# Power_Amp_V1_0.net
KiCad netlist of a schematic drawn in EAGLE
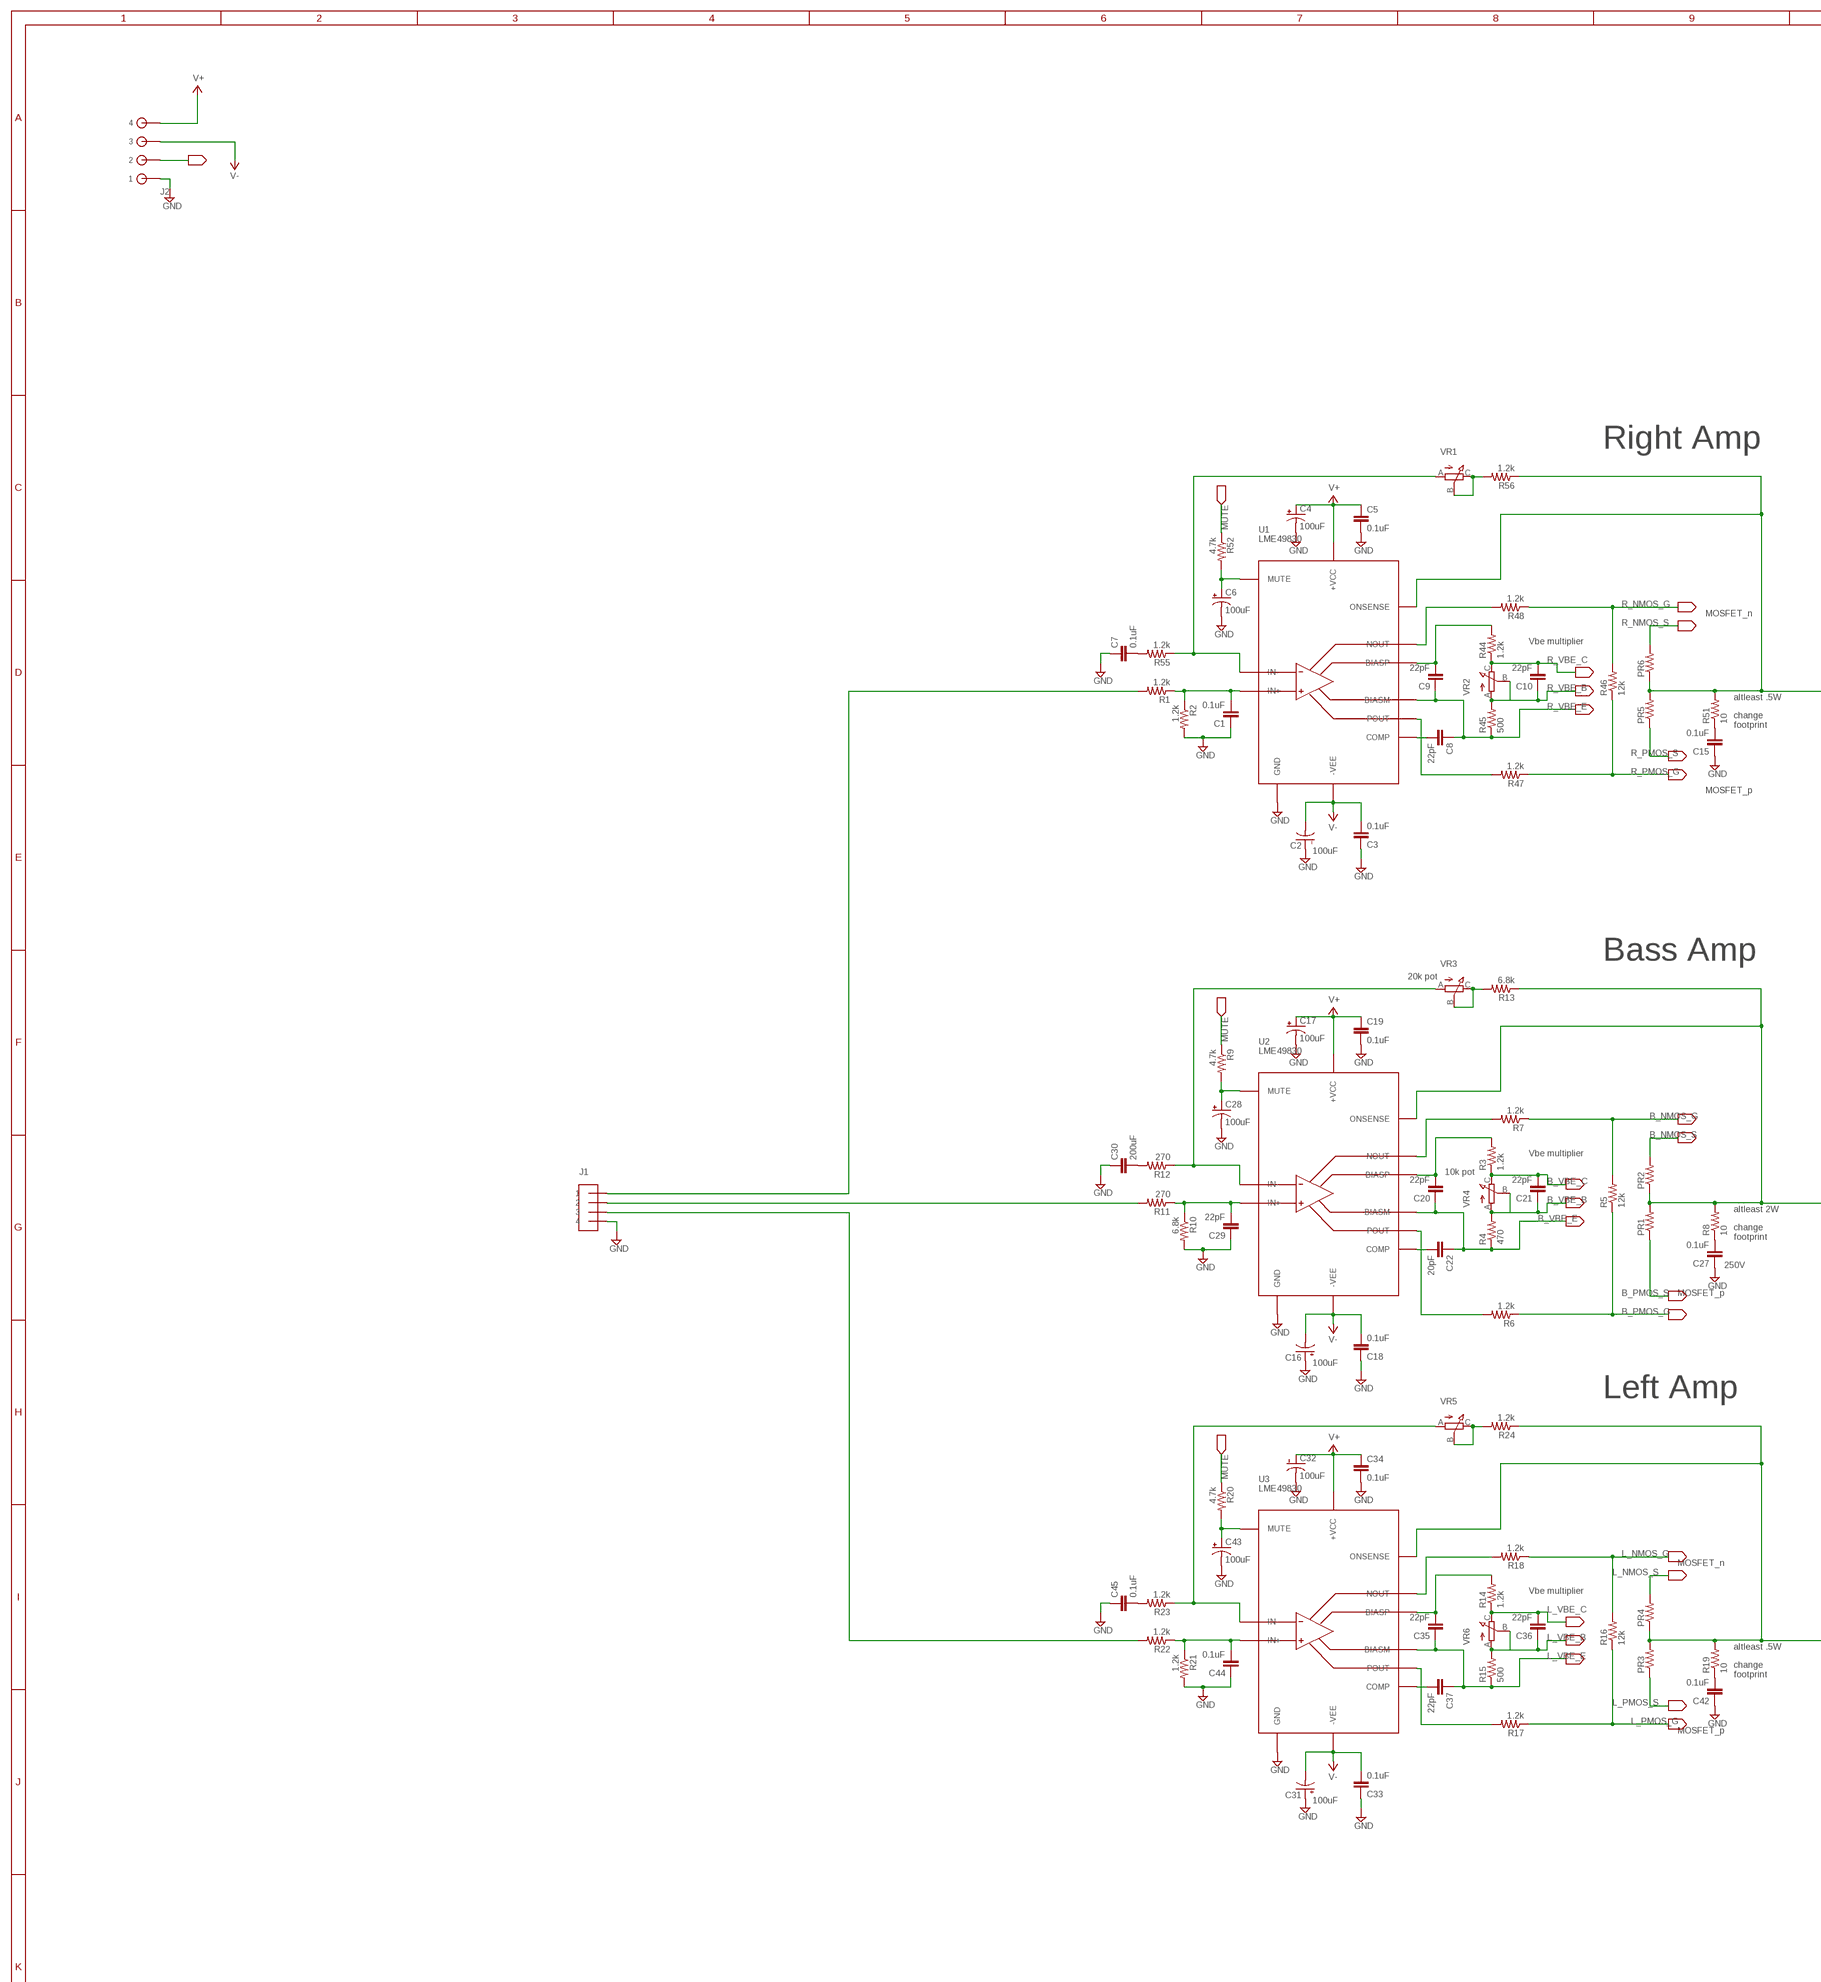
[diagram p0: schematic, sheet 1, part 1 of 3]
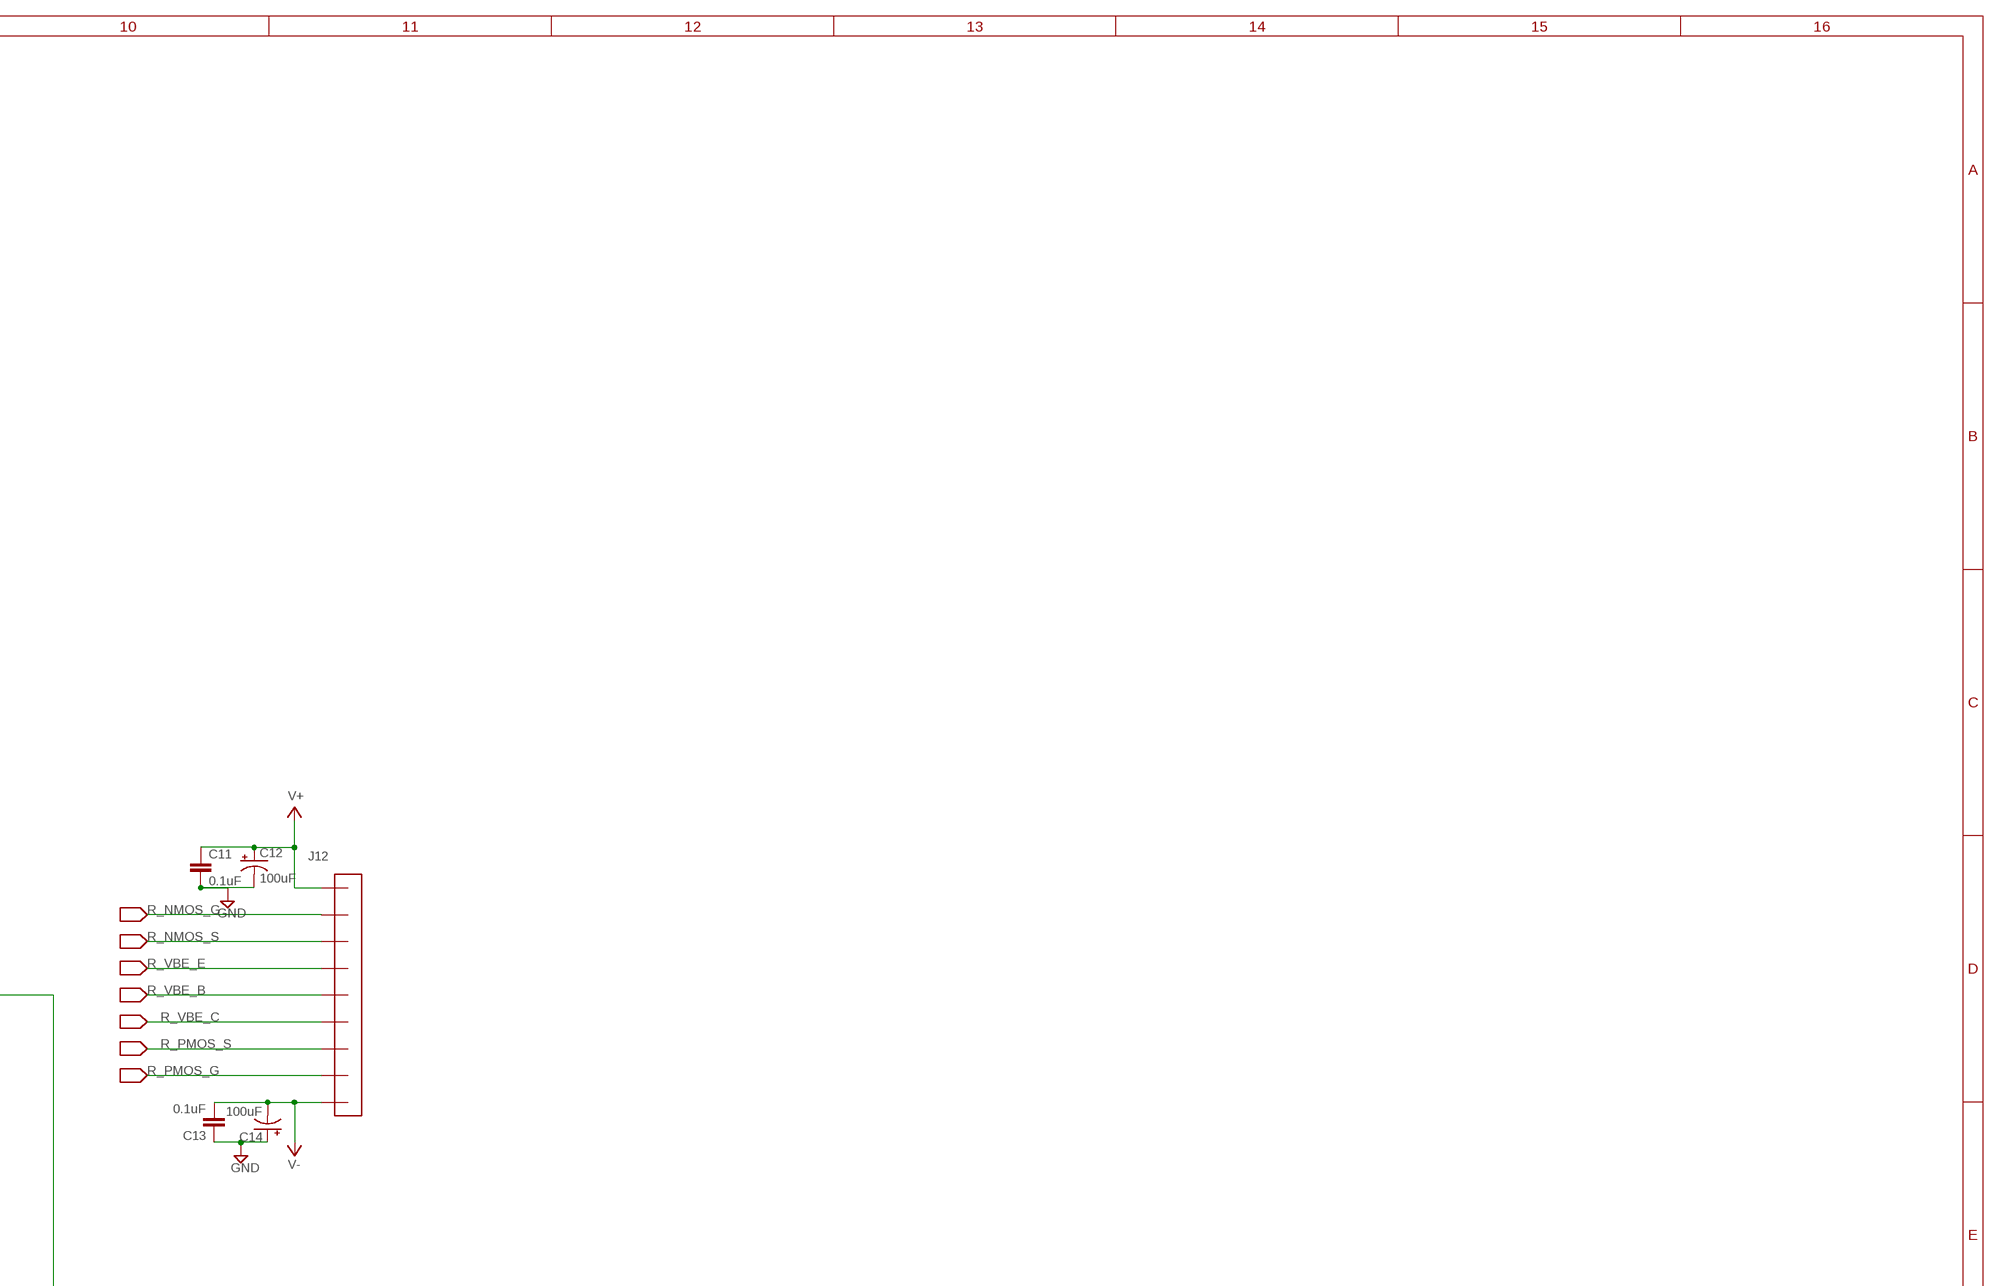
[diagram p1: schematic, sheet 1, part 2 of 3]
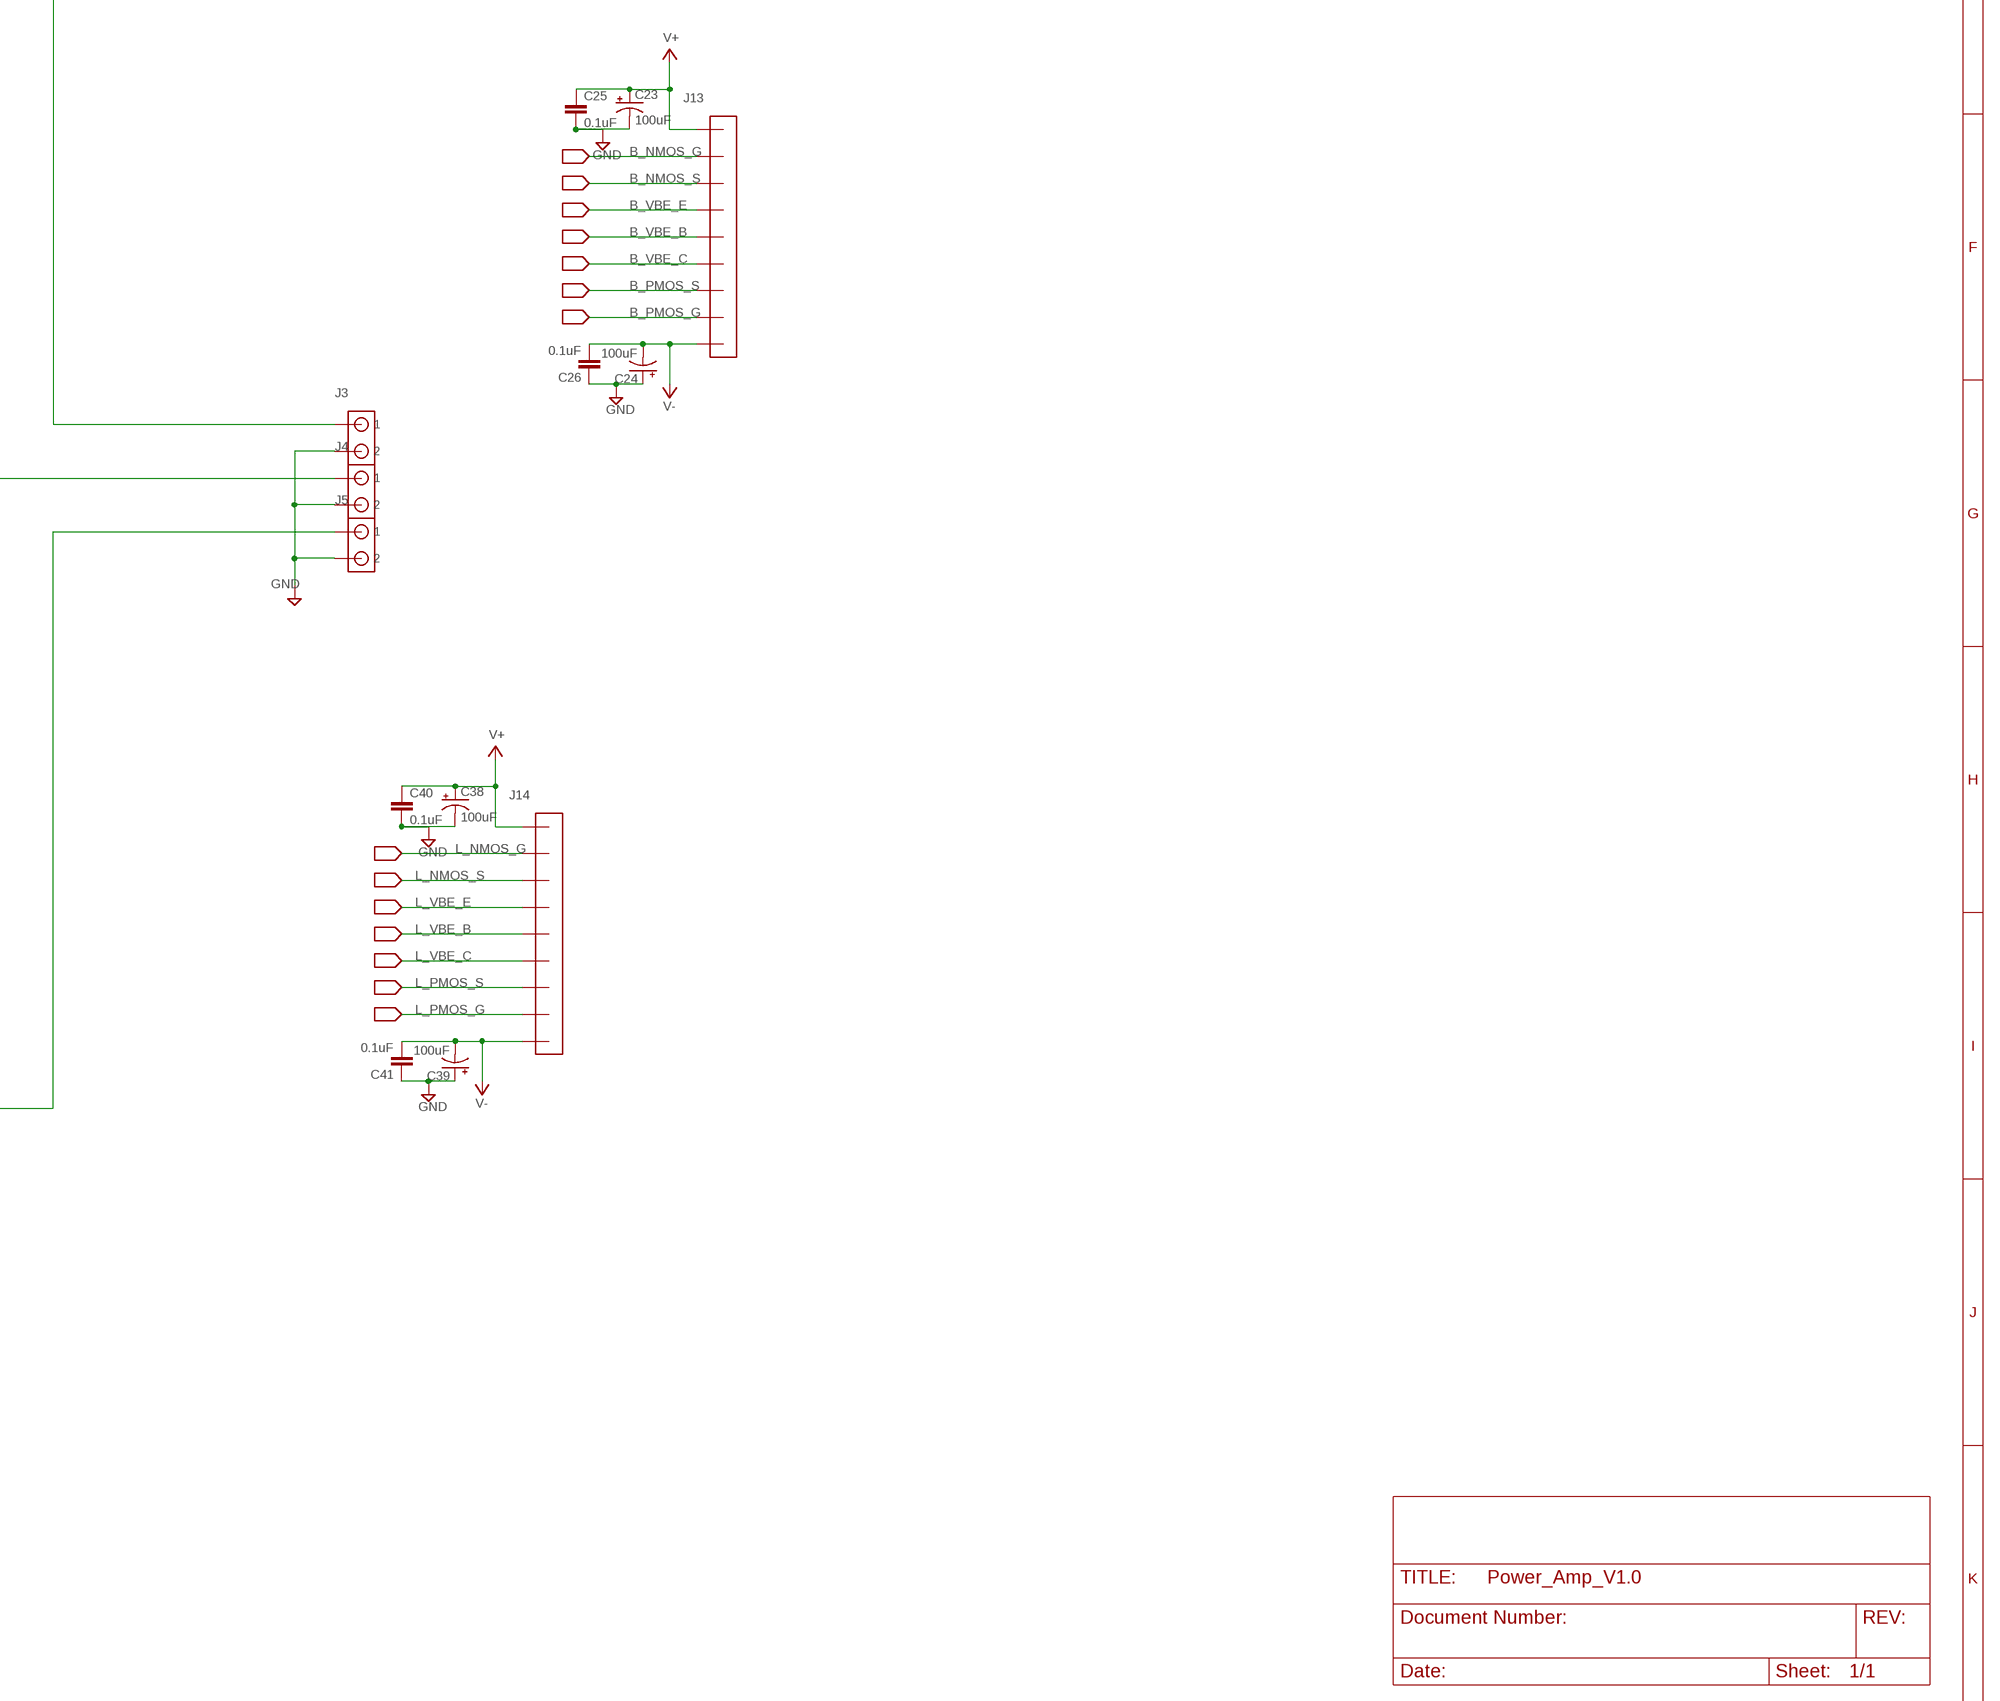
[diagram p2: schematic, sheet 1, part 3 of 3]

(export (version "E")
  (design (tool "Eeschema 10.0.6"))
  (components
    (comp (ref "C1")
      (value "0.1uF")
      (footprint "eagle-import:C050-024X044")
      (libsource (lib "eagle-import") (part "C-EU050-024X044"))
    )
    (comp (ref "C2")
      (value "100uF")
      (footprint "eagle-import:E2,5-6")
      (libsource (lib "eagle-import") (part "CPOL-USE2.5-6"))
    )
    (comp (ref "C3")
      (value "0.1uF")
      (footprint "eagle-import:C050-024X044")
      (libsource (lib "eagle-import") (part "C-EU050-024X044"))
    )
    (comp (ref "C4")
      (value "100uF")
      (footprint "eagle-import:E2,5-6")
      (libsource (lib "eagle-import") (part "CPOL-USE2.5-6"))
    )
    (comp (ref "C5")
      (value "0.1uF")
      (footprint "eagle-import:C050-024X044")
      (libsource (lib "eagle-import") (part "C-EU050-024X044"))
    )
    (comp (ref "C6")
      (value "100uF")
      (footprint "eagle-import:E2,5-6")
      (libsource (lib "eagle-import") (part "CPOL-USE2.5-6"))
    )
    (comp (ref "C7")
      (value "0.1uF")
      (footprint "eagle-import:C050-024X044")
      (libsource (lib "eagle-import") (part "C-EU050-024X044"))
    )
    (comp (ref "C8")
      (value "22pF")
      (footprint "eagle-import:C050-024X044")
      (libsource (lib "eagle-import") (part "C-EU050-024X044"))
    )
    (comp (ref "C9")
      (value "22pF")
      (footprint "eagle-import:C050-024X044")
      (libsource (lib "eagle-import") (part "C-EU050-024X044"))
    )
    (comp (ref "C10")
      (value "22pF")
      (footprint "eagle-import:C050-024X044")
      (libsource (lib "eagle-import") (part "C-EU050-024X044"))
    )
    (comp (ref "C11")
      (value "0.1uF")
      (footprint "eagle-import:C050-024X044")
      (libsource (lib "eagle-import") (part "C-EU050-024X044"))
    )
    (comp (ref "C12")
      (value "100uF")
      (footprint "eagle-import:E2,5-6")
      (libsource (lib "eagle-import") (part "CPOL-USE2.5-6"))
    )
    (comp (ref "C13")
      (value "0.1uF")
      (footprint "eagle-import:C050-024X044")
      (libsource (lib "eagle-import") (part "C-EU050-024X044"))
    )
    (comp (ref "C14")
      (value "100uF")
      (footprint "eagle-import:E2,5-6")
      (libsource (lib "eagle-import") (part "CPOL-USE2.5-6"))
    )
    (comp (ref "C15")
      (value "0.1uF")
      (footprint "eagle-import:C050-024X044")
      (libsource (lib "eagle-import") (part "C-EU050-024X044"))
    )
    (comp (ref "C16")
      (value "100uF")
      (footprint "eagle-import:E2,5-6")
      (libsource (lib "eagle-import") (part "CPOL-USE2.5-6"))
    )
    (comp (ref "C17")
      (value "100uF")
      (footprint "eagle-import:E2,5-6")
      (libsource (lib "eagle-import") (part "CPOL-USE2.5-6"))
    )
    (comp (ref "C18")
      (value "0.1uF")
      (footprint "eagle-import:C050-024X044")
      (libsource (lib "eagle-import") (part "C-EU050-024X044"))
    )
    (comp (ref "C19")
      (value "0.1uF")
      (footprint "eagle-import:C050-024X044")
      (libsource (lib "eagle-import") (part "C-EU050-024X044"))
    )
    (comp (ref "C20")
      (value "22pF")
      (footprint "eagle-import:C050-024X044")
      (libsource (lib "eagle-import") (part "C-EU050-024X044"))
    )
    (comp (ref "C21")
      (value "22pF")
      (footprint "eagle-import:C050-024X044")
      (libsource (lib "eagle-import") (part "C-EU050-024X044"))
    )
    (comp (ref "C22")
      (value "20pF")
      (footprint "eagle-import:C050-024X044")
      (libsource (lib "eagle-import") (part "C-EU050-024X044"))
    )
    (comp (ref "C23")
      (value "100uF")
      (footprint "eagle-import:E2,5-6")
      (libsource (lib "eagle-import") (part "CPOL-USE2.5-6"))
    )
    (comp (ref "C24")
      (value "100uF")
      (footprint "eagle-import:E2,5-6")
      (libsource (lib "eagle-import") (part "CPOL-USE2.5-6"))
    )
    (comp (ref "C25")
      (value "0.1uF")
      (footprint "eagle-import:C050-024X044")
      (libsource (lib "eagle-import") (part "C-EU050-024X044"))
    )
    (comp (ref "C26")
      (value "0.1uF")
      (footprint "eagle-import:C050-024X044")
      (libsource (lib "eagle-import") (part "C-EU050-024X044"))
    )
    (comp (ref "C27")
      (value "0.1uF")
      (footprint "eagle-import:C050-024X044")
      (libsource (lib "eagle-import") (part "C-EU050-024X044"))
    )
    (comp (ref "C28")
      (value "100uF")
      (footprint "eagle-import:E2,5-6")
      (libsource (lib "eagle-import") (part "CPOL-USE2.5-6"))
    )
    (comp (ref "C29")
      (value "22pF")
      (footprint "eagle-import:C050-024X044")
      (libsource (lib "eagle-import") (part "C-EU050-024X044"))
    )
    (comp (ref "C30")
      (value "200uF")
      (footprint "eagle-import:C050-024X044")
      (libsource (lib "eagle-import") (part "C-EU050-024X044"))
    )
    (comp (ref "C31")
      (value "100uF")
      (footprint "eagle-import:E2,5-6")
      (libsource (lib "eagle-import") (part "CPOL-USE2.5-6"))
    )
    (comp (ref "C32")
      (value "100uF")
      (footprint "eagle-import:E2,5-6")
      (libsource (lib "eagle-import") (part "CPOL-USE2.5-6"))
    )
    (comp (ref "C33")
      (value "0.1uF")
      (footprint "eagle-import:C050-024X044")
      (libsource (lib "eagle-import") (part "C-EU050-024X044"))
    )
    (comp (ref "C34")
      (value "0.1uF")
      (footprint "eagle-import:C050-024X044")
      (libsource (lib "eagle-import") (part "C-EU050-024X044"))
    )
    (comp (ref "C35")
      (value "22pF")
      (footprint "eagle-import:C050-024X044")
      (libsource (lib "eagle-import") (part "C-EU050-024X044"))
    )
    (comp (ref "C36")
      (value "22pF")
      (footprint "eagle-import:C050-024X044")
      (libsource (lib "eagle-import") (part "C-EU050-024X044"))
    )
    (comp (ref "C37")
      (value "22pF")
      (footprint "eagle-import:C050-024X044")
      (libsource (lib "eagle-import") (part "C-EU050-024X044"))
    )
    (comp (ref "C38")
      (value "100uF")
      (footprint "eagle-import:E2,5-6")
      (libsource (lib "eagle-import") (part "CPOL-USE2.5-6"))
    )
    (comp (ref "C39")
      (value "100uF")
      (footprint "eagle-import:E2,5-6")
      (libsource (lib "eagle-import") (part "CPOL-USE2.5-6"))
    )
    (comp (ref "C40")
      (value "0.1uF")
      (footprint "eagle-import:C050-024X044")
      (libsource (lib "eagle-import") (part "C-EU050-024X044"))
    )
    (comp (ref "C41")
      (value "0.1uF")
      (footprint "eagle-import:C050-024X044")
      (libsource (lib "eagle-import") (part "C-EU050-024X044"))
    )
    (comp (ref "C42")
      (value "0.1uF")
      (footprint "eagle-import:C050-024X044")
      (libsource (lib "eagle-import") (part "C-EU050-024X044"))
    )
    (comp (ref "C43")
      (value "100uF")
      (footprint "eagle-import:E2,5-6")
      (libsource (lib "eagle-import") (part "CPOL-USE2.5-6"))
    )
    (comp (ref "C44")
      (value "0.1uF")
      (footprint "eagle-import:C050-024X044")
      (libsource (lib "eagle-import") (part "C-EU050-024X044"))
    )
    (comp (ref "C45")
      (value "0.1uF")
      (footprint "eagle-import:C050-024X044")
      (libsource (lib "eagle-import") (part "C-EU050-024X044"))
    )
    (comp (ref "J1")
      (value "4_PIN_AMPCONN")
      (footprint "eagle-import:4_PIN_AMPCON")
      (libsource (lib "eagle-import") (part "4_PIN_AMPCONN"))
    )
    (comp (ref "J2")
      (value "1984633")
      (footprint "eagle-import:1984633")
      (libsource (lib "eagle-import") (part "1984633"))
    )
    (comp (ref "J3")
      (value "2TERMINAL_SPEAKER")
      (footprint "eagle-import:2TERMINAL_SPEAKER")
      (libsource (lib "eagle-import") (part "2TERMINAL_SPEAKER"))
    )
    (comp (ref "J4")
      (value "2TERMINAL_SPEAKER")
      (footprint "eagle-import:2TERMINAL_SPEAKER")
      (libsource (lib "eagle-import") (part "2TERMINAL_SPEAKER"))
    )
    (comp (ref "J5")
      (value "2TERMINAL_SPEAKER")
      (footprint "eagle-import:2TERMINAL_SPEAKER")
      (libsource (lib "eagle-import") (part "2TERMINAL_SPEAKER"))
    )
    (comp (ref "J12")
      (value "1725724")
      (footprint "eagle-import:1725724")
      (libsource (lib "eagle-import") (part "1725724"))
    )
    (comp (ref "J13")
      (value "1725724")
      (footprint "eagle-import:1725724")
      (libsource (lib "eagle-import") (part "1725724"))
    )
    (comp (ref "J14")
      (value "1725724")
      (footprint "eagle-import:1725724")
      (libsource (lib "eagle-import") (part "1725724"))
    )
    (comp (ref "PR1")
      (value "R-US_0617/5V")
      (footprint "eagle-import:0617V")
      (libsource (lib "eagle-import") (part "R-US_0617/5V"))
    )
    (comp (ref "PR2")
      (value "R-US_0617/5V")
      (footprint "eagle-import:0617V")
      (libsource (lib "eagle-import") (part "R-US_0617/5V"))
    )
    (comp (ref "PR3")
      (value "R-US_0617/5V")
      (footprint "eagle-import:0617V")
      (libsource (lib "eagle-import") (part "R-US_0617/5V"))
    )
    (comp (ref "PR4")
      (value "R-US_0617/5V")
      (footprint "eagle-import:0617V")
      (libsource (lib "eagle-import") (part "R-US_0617/5V"))
    )
    (comp (ref "PR5")
      (value "R-US_0617/5V")
      (footprint "eagle-import:0617V")
      (libsource (lib "eagle-import") (part "R-US_0617/5V"))
    )
    (comp (ref "PR6")
      (value "R-US_0617/5V")
      (footprint "eagle-import:0617V")
      (libsource (lib "eagle-import") (part "R-US_0617/5V"))
    )
    (comp (ref "R1")
      (value "1.2k")
      (footprint "eagle-import:0204V")
      (libsource (lib "eagle-import") (part "R-US_0204/2V"))
    )
    (comp (ref "R2")
      (value "1.2k")
      (footprint "eagle-import:0204V")
      (libsource (lib "eagle-import") (part "R-US_0204/2V"))
    )
    (comp (ref "R3")
      (value "1.2k")
      (footprint "eagle-import:0204V")
      (libsource (lib "eagle-import") (part "R-US_0204/2V"))
    )
    (comp (ref "R4")
      (value "470")
      (footprint "eagle-import:0204V")
      (libsource (lib "eagle-import") (part "R-US_0204/2V"))
    )
    (comp (ref "R5")
      (value "12k")
      (footprint "eagle-import:0204V")
      (libsource (lib "eagle-import") (part "R-US_0204/2V"))
    )
    (comp (ref "R6")
      (value "1.2k")
      (footprint "eagle-import:0204V")
      (libsource (lib "eagle-import") (part "R-US_0204/2V"))
    )
    (comp (ref "R7")
      (value "1.2k")
      (footprint "eagle-import:0204V")
      (libsource (lib "eagle-import") (part "R-US_0204/2V"))
    )
    (comp (ref "R8")
      (value "10")
      (footprint "eagle-import:0309V")
      (libsource (lib "eagle-import") (part "R-US_0309/V"))
    )
    (comp (ref "R9")
      (value "4.7k")
      (footprint "eagle-import:0204V")
      (libsource (lib "eagle-import") (part "R-US_0204/2V"))
    )
    (comp (ref "R10")
      (value "6.8k")
      (footprint "eagle-import:0204V")
      (libsource (lib "eagle-import") (part "R-US_0204/2V"))
    )
    (comp (ref "R11")
      (value "270")
      (footprint "eagle-import:0204V")
      (libsource (lib "eagle-import") (part "R-US_0204/2V"))
    )
    (comp (ref "R12")
      (value "270")
      (footprint "eagle-import:0204V")
      (libsource (lib "eagle-import") (part "R-US_0204/2V"))
    )
    (comp (ref "R13")
      (value "6.8k")
      (footprint "eagle-import:0204V")
      (libsource (lib "eagle-import") (part "R-US_0204/2V"))
    )
    (comp (ref "R14")
      (value "1.2k")
      (footprint "eagle-import:0204V")
      (libsource (lib "eagle-import") (part "R-US_0204/2V"))
    )
    (comp (ref "R15")
      (value "500")
      (footprint "eagle-import:0204V")
      (libsource (lib "eagle-import") (part "R-US_0204/2V"))
    )
    (comp (ref "R16")
      (value "12k")
      (footprint "eagle-import:0204V")
      (libsource (lib "eagle-import") (part "R-US_0204/2V"))
    )
    (comp (ref "R17")
      (value "1.2k")
      (footprint "eagle-import:0204V")
      (libsource (lib "eagle-import") (part "R-US_0204/2V"))
    )
    (comp (ref "R18")
      (value "1.2k")
      (footprint "eagle-import:0204V")
      (libsource (lib "eagle-import") (part "R-US_0204/2V"))
    )
    (comp (ref "R19")
      (value "10")
      (footprint "eagle-import:0309V")
      (libsource (lib "eagle-import") (part "R-US_0309/V"))
    )
    (comp (ref "R20")
      (value "4.7k")
      (footprint "eagle-import:0204V")
      (libsource (lib "eagle-import") (part "R-US_0204/2V"))
    )
    (comp (ref "R21")
      (value "1.2k")
      (footprint "eagle-import:0204V")
      (libsource (lib "eagle-import") (part "R-US_0204/2V"))
    )
    (comp (ref "R22")
      (value "1.2k")
      (footprint "eagle-import:0204V")
      (libsource (lib "eagle-import") (part "R-US_0204/2V"))
    )
    (comp (ref "R23")
      (value "1.2k")
      (footprint "eagle-import:0204V")
      (libsource (lib "eagle-import") (part "R-US_0204/2V"))
    )
    (comp (ref "R24")
      (value "1.2k")
      (footprint "eagle-import:0204V")
      (libsource (lib "eagle-import") (part "R-US_0204/2V"))
    )
    (comp (ref "R44")
      (value "1.2k")
      (footprint "eagle-import:0204V")
      (libsource (lib "eagle-import") (part "R-US_0204/2V"))
    )
    (comp (ref "R45")
      (value "500")
      (footprint "eagle-import:0204V")
      (libsource (lib "eagle-import") (part "R-US_0204/2V"))
    )
    (comp (ref "R46")
      (value "12k")
      (footprint "eagle-import:0204V")
      (libsource (lib "eagle-import") (part "R-US_0204/2V"))
    )
    (comp (ref "R47")
      (value "1.2k")
      (footprint "eagle-import:0204V")
      (libsource (lib "eagle-import") (part "R-US_0204/2V"))
    )
    (comp (ref "R48")
      (value "1.2k")
      (footprint "eagle-import:0204V")
      (libsource (lib "eagle-import") (part "R-US_0204/2V"))
    )
    (comp (ref "R51")
      (value "10")
      (footprint "eagle-import:0309V")
      (libsource (lib "eagle-import") (part "R-US_0309/V"))
    )
    (comp (ref "R52")
      (value "4.7k")
      (footprint "eagle-import:0204V")
      (libsource (lib "eagle-import") (part "R-US_0204/2V"))
    )
    (comp (ref "R55")
      (value "1.2k")
      (footprint "eagle-import:0204V")
      (libsource (lib "eagle-import") (part "R-US_0204/2V"))
    )
    (comp (ref "R56")
      (value "1.2k")
      (footprint "eagle-import:0204V")
      (libsource (lib "eagle-import") (part "R-US_0204/2V"))
    )
    (comp (ref "U1")
      (value "LME49830")
      (footprint "eagle-import:NDN0015A")
      (libsource (lib "eagle-import") (part "LME49830"))
    )
    (comp (ref "U2")
      (value "LME49830")
      (footprint "eagle-import:NDN0015A")
      (libsource (lib "eagle-import") (part "LME49830"))
    )
    (comp (ref "U3")
      (value "LME49830")
      (footprint "eagle-import:NDN0015A")
      (libsource (lib "eagle-import") (part "LME49830"))
    )
    (comp (ref "VR1")
      (value "EVM2W")
      (footprint "eagle-import:EVM2W")
      (libsource (lib "eagle-import") (part "EVM2W"))
    )
    (comp (ref "VR2")
      (value "EVM2W")
      (footprint "eagle-import:EVM2W")
      (libsource (lib "eagle-import") (part "EVM2W"))
    )
    (comp (ref "VR3")
      (value "EVM2W")
      (footprint "eagle-import:EVM2W")
      (libsource (lib "eagle-import") (part "EVM2W"))
    )
    (comp (ref "VR4")
      (value "EVM2W")
      (footprint "eagle-import:EVM2W")
      (libsource (lib "eagle-import") (part "EVM2W"))
    )
    (comp (ref "VR5")
      (value "EVM2W")
      (footprint "eagle-import:EVM2W")
      (libsource (lib "eagle-import") (part "EVM2W"))
    )
    (comp (ref "VR6")
      (value "EVM2W")
      (footprint "eagle-import:EVM2W")
      (libsource (lib "eagle-import") (part "EVM2W"))
    )
  )
  (nets
    (net (code "1") (name "/B_NMOS_G") (class "Default")
      (node (ref "J13") (pin "P$2") (pinfunction "2_P$2") (pintype "passive"))
      (node (ref "R5") (pin "2") (pinfunction "2_2") (pintype "passive"))
      (node (ref "R7") (pin "1") (pinfunction "1_1") (pintype "passive"))
    )
    (net (code "2") (name "/B_NMOS_S") (class "Default")
      (node (ref "J13") (pin "P$3") (pinfunction "3_P$3") (pintype "passive"))
      (node (ref "PR2") (pin "2") (pinfunction "2_2") (pintype "passive"))
    )
    (net (code "3") (name "/B_PMOS_G") (class "Default")
      (node (ref "J13") (pin "P$8") (pinfunction "8_P$8") (pintype "passive"))
      (node (ref "R5") (pin "1") (pinfunction "1_1") (pintype "passive"))
      (node (ref "R6") (pin "1") (pinfunction "1_1") (pintype "passive"))
    )
    (net (code "4") (name "/B_PMOS_S") (class "Default")
      (node (ref "J13") (pin "P$7") (pinfunction "7_P$7") (pintype "passive"))
      (node (ref "PR1") (pin "1") (pinfunction "1_1") (pintype "passive"))
    )
    (net (code "5") (name "/B_VBE_B") (class "Default")
      (node (ref "C21") (pin "1") (pinfunction "1_1") (pintype "passive"))
      (node (ref "J13") (pin "P$5") (pinfunction "5_P$5") (pintype "passive"))
      (node (ref "R4") (pin "2") (pinfunction "2_2") (pintype "passive"))
      (node (ref "VR4") (pin "A") (pinfunction "A_A") (pintype "passive"))
      (node (ref "VR4") (pin "B") (pinfunction "B_B") (pintype "passive"))
    )
    (net (code "6") (name "/B_VBE_C") (class "Default")
      (node (ref "C21") (pin "2") (pinfunction "2_2") (pintype "passive"))
      (node (ref "J13") (pin "P$6") (pinfunction "6_P$6") (pintype "passive"))
      (node (ref "R3") (pin "1") (pinfunction "1_1") (pintype "passive"))
      (node (ref "VR4") (pin "C") (pinfunction "C_C") (pintype "passive"))
    )
    (net (code "7") (name "/B_VBE_E") (class "Default")
      (node (ref "C20") (pin "1") (pinfunction "1_1") (pintype "passive"))
      (node (ref "C22") (pin "1") (pinfunction "1_1") (pintype "passive"))
      (node (ref "J13") (pin "P$4") (pinfunction "4_P$4") (pintype "passive"))
      (node (ref "R4") (pin "1") (pinfunction "1_1") (pintype "passive"))
      (node (ref "U2") (pin "P11") (pinfunction "BIASM_P11") (pintype "bidirectional"))
    )
    (net (code "8") (name "/L_NMOS_G") (class "Default")
      (node (ref "J14") (pin "P$2") (pinfunction "2_P$2") (pintype "passive"))
      (node (ref "R16") (pin "2") (pinfunction "2_2") (pintype "passive"))
      (node (ref "R18") (pin "1") (pinfunction "1_1") (pintype "passive"))
    )
    (net (code "9") (name "/L_NMOS_S") (class "Default")
      (node (ref "J14") (pin "P$3") (pinfunction "3_P$3") (pintype "passive"))
      (node (ref "PR4") (pin "2") (pinfunction "2_2") (pintype "passive"))
    )
    (net (code "10") (name "/L_PMOS_G") (class "Default")
      (node (ref "J14") (pin "P$8") (pinfunction "8_P$8") (pintype "passive"))
      (node (ref "R16") (pin "1") (pinfunction "1_1") (pintype "passive"))
      (node (ref "R17") (pin "1") (pinfunction "1_1") (pintype "passive"))
    )
    (net (code "11") (name "/L_PMOS_S") (class "Default")
      (node (ref "J14") (pin "P$7") (pinfunction "7_P$7") (pintype "passive"))
      (node (ref "PR3") (pin "1") (pinfunction "1_1") (pintype "passive"))
    )
    (net (code "12") (name "/L_VBE_B") (class "Default")
      (node (ref "C36") (pin "1") (pinfunction "1_1") (pintype "passive"))
      (node (ref "J14") (pin "P$5") (pinfunction "5_P$5") (pintype "passive"))
      (node (ref "R15") (pin "2") (pinfunction "2_2") (pintype "passive"))
      (node (ref "VR6") (pin "A") (pinfunction "A_A") (pintype "passive"))
      (node (ref "VR6") (pin "B") (pinfunction "B_B") (pintype "passive"))
    )
    (net (code "13") (name "/L_VBE_C") (class "Default")
      (node (ref "C36") (pin "2") (pinfunction "2_2") (pintype "passive"))
      (node (ref "J14") (pin "P$6") (pinfunction "6_P$6") (pintype "passive"))
      (node (ref "R14") (pin "1") (pinfunction "1_1") (pintype "passive"))
      (node (ref "VR6") (pin "C") (pinfunction "C_C") (pintype "passive"))
    )
    (net (code "14") (name "/L_VBE_E") (class "Default")
      (node (ref "C35") (pin "1") (pinfunction "1_1") (pintype "passive"))
      (node (ref "C37") (pin "1") (pinfunction "1_1") (pintype "passive"))
      (node (ref "J14") (pin "P$4") (pinfunction "4_P$4") (pintype "passive"))
      (node (ref "R15") (pin "1") (pinfunction "1_1") (pintype "passive"))
      (node (ref "U3") (pin "P11") (pinfunction "BIASM_P11") (pintype "bidirectional"))
    )
    (net (code "15") (name "/MUTE") (class "Default")
      (node (ref "J2") (pin "P$2") (pinfunction "2_P$2") (pintype "passive"))
      (node (ref "R20") (pin "1") (pinfunction "1_1") (pintype "passive"))
      (node (ref "R52") (pin "1") (pinfunction "1_1") (pintype "passive"))
      (node (ref "R9") (pin "1") (pinfunction "1_1") (pintype "passive"))
    )
    (net (code "16") (name "/R_NMOS_G") (class "Default")
      (node (ref "J12") (pin "P$2") (pinfunction "2_P$2") (pintype "passive"))
      (node (ref "R46") (pin "2") (pinfunction "2_2") (pintype "passive"))
      (node (ref "R48") (pin "1") (pinfunction "1_1") (pintype "passive"))
    )
    (net (code "17") (name "/R_NMOS_S") (class "Default")
      (node (ref "J12") (pin "P$3") (pinfunction "3_P$3") (pintype "passive"))
      (node (ref "PR6") (pin "2") (pinfunction "2_2") (pintype "passive"))
    )
    (net (code "18") (name "/R_PMOS_G") (class "Default")
      (node (ref "J12") (pin "P$8") (pinfunction "8_P$8") (pintype "passive"))
      (node (ref "R46") (pin "1") (pinfunction "1_1") (pintype "passive"))
      (node (ref "R47") (pin "1") (pinfunction "1_1") (pintype "passive"))
    )
    (net (code "19") (name "/R_PMOS_S") (class "Default")
      (node (ref "J12") (pin "P$7") (pinfunction "7_P$7") (pintype "passive"))
      (node (ref "PR5") (pin "1") (pinfunction "1_1") (pintype "passive"))
    )
    (net (code "20") (name "/R_VBE_B") (class "Default")
      (node (ref "C10") (pin "1") (pinfunction "1_1") (pintype "passive"))
      (node (ref "J12") (pin "P$5") (pinfunction "5_P$5") (pintype "passive"))
      (node (ref "R45") (pin "2") (pinfunction "2_2") (pintype "passive"))
      (node (ref "VR2") (pin "A") (pinfunction "A_A") (pintype "passive"))
      (node (ref "VR2") (pin "B") (pinfunction "B_B") (pintype "passive"))
    )
    (net (code "21") (name "/R_VBE_C") (class "Default")
      (node (ref "C10") (pin "2") (pinfunction "2_2") (pintype "passive"))
      (node (ref "J12") (pin "P$6") (pinfunction "6_P$6") (pintype "passive"))
      (node (ref "R44") (pin "1") (pinfunction "1_1") (pintype "passive"))
      (node (ref "VR2") (pin "C") (pinfunction "C_C") (pintype "passive"))
    )
    (net (code "22") (name "/R_VBE_E") (class "Default")
      (node (ref "C8") (pin "1") (pinfunction "1_1") (pintype "passive"))
      (node (ref "C9") (pin "1") (pinfunction "1_1") (pintype "passive"))
      (node (ref "J12") (pin "P$4") (pinfunction "4_P$4") (pintype "passive"))
      (node (ref "R45") (pin "1") (pinfunction "1_1") (pintype "passive"))
      (node (ref "U1") (pin "P11") (pinfunction "BIASM_P11") (pintype "bidirectional"))
    )
    (net (code "23") (name "GND") (class "Default")
      (node (ref "C1") (pin "1") (pinfunction "1_1") (pintype "passive"))
      (node (ref "C11") (pin "2") (pinfunction "2_2") (pintype "passive"))
      (node (ref "C12") (pin "-") (pinfunction "-_-") (pintype "passive"))
      (node (ref "C13") (pin "1") (pinfunction "1_1") (pintype "passive"))
      (node (ref "C14") (pin "+") (pinfunction "+_+") (pintype "passive"))
      (node (ref "C15") (pin "1") (pinfunction "1_1") (pintype "passive"))
      (node (ref "C16") (pin "+") (pinfunction "+_+") (pintype "passive"))
      (node (ref "C17") (pin "-") (pinfunction "-_-") (pintype "passive"))
      (node (ref "C18") (pin "1") (pinfunction "1_1") (pintype "passive"))
      (node (ref "C19") (pin "2") (pinfunction "2_2") (pintype "passive"))
      (node (ref "C2") (pin "+") (pinfunction "+_+") (pintype "passive"))
      (node (ref "C23") (pin "-") (pinfunction "-_-") (pintype "passive"))
      (node (ref "C24") (pin "+") (pinfunction "+_+") (pintype "passive"))
      (node (ref "C25") (pin "2") (pinfunction "2_2") (pintype "passive"))
      (node (ref "C26") (pin "1") (pinfunction "1_1") (pintype "passive"))
      (node (ref "C27") (pin "1") (pinfunction "1_1") (pintype "passive"))
      (node (ref "C28") (pin "-") (pinfunction "-_-") (pintype "passive"))
      (node (ref "C29") (pin "1") (pinfunction "1_1") (pintype "passive"))
      (node (ref "C3") (pin "1") (pinfunction "1_1") (pintype "passive"))
      (node (ref "C30") (pin "1") (pinfunction "1_1") (pintype "passive"))
      (node (ref "C31") (pin "+") (pinfunction "+_+") (pintype "passive"))
      (node (ref "C32") (pin "-") (pinfunction "-_-") (pintype "passive"))
      (node (ref "C33") (pin "1") (pinfunction "1_1") (pintype "passive"))
      (node (ref "C34") (pin "2") (pinfunction "2_2") (pintype "passive"))
      (node (ref "C38") (pin "-") (pinfunction "-_-") (pintype "passive"))
      (node (ref "C39") (pin "+") (pinfunction "+_+") (pintype "passive"))
      (node (ref "C4") (pin "-") (pinfunction "-_-") (pintype "passive"))
      (node (ref "C40") (pin "2") (pinfunction "2_2") (pintype "passive"))
      (node (ref "C41") (pin "1") (pinfunction "1_1") (pintype "passive"))
      (node (ref "C42") (pin "1") (pinfunction "1_1") (pintype "passive"))
      (node (ref "C43") (pin "-") (pinfunction "-_-") (pintype "passive"))
      (node (ref "C44") (pin "1") (pinfunction "1_1") (pintype "passive"))
      (node (ref "C45") (pin "1") (pinfunction "1_1") (pintype "passive"))
      (node (ref "C5") (pin "2") (pinfunction "2_2") (pintype "passive"))
      (node (ref "C6") (pin "-") (pinfunction "-_-") (pintype "passive"))
      (node (ref "C7") (pin "1") (pinfunction "1_1") (pintype "passive"))
      (node (ref "J1") (pin "4") (pinfunction "4_4") (pintype "passive"))
      (node (ref "J2") (pin "P$1") (pinfunction "1_P$1") (pintype "passive"))
      (node (ref "J3") (pin "P$2") (pinfunction "2_P$2") (pintype "passive"))
      (node (ref "J4") (pin "P$2") (pinfunction "2_P$2") (pintype "passive"))
      (node (ref "J5") (pin "P$2") (pinfunction "2_P$2") (pintype "passive"))
      (node (ref "R10") (pin "2") (pinfunction "2_2") (pintype "passive"))
      (node (ref "R2") (pin "2") (pinfunction "2_2") (pintype "passive"))
      (node (ref "R21") (pin "2") (pinfunction "2_2") (pintype "passive"))
      (node (ref "U1") (pin "P3") (pinfunction "GND_P3") (pintype "bidirectional"))
      (node (ref "U2") (pin "P3") (pinfunction "GND_P3") (pintype "bidirectional"))
      (node (ref "U3") (pin "P3") (pinfunction "GND_P3") (pintype "bidirectional"))
    )
    (net (code "24") (name "Net-(C7-Pad2)") (class "Default")
      (node (ref "C7") (pin "2") (pinfunction "2_2") (pintype "passive"))
      (node (ref "R55") (pin "2") (pinfunction "2_2") (pintype "passive"))
    )
    (net (code "25") (name "Net-(C15-Pad2)") (class "Default")
      (node (ref "C15") (pin "2") (pinfunction "2_2") (pintype "passive"))
      (node (ref "R51") (pin "1") (pinfunction "1_1") (pintype "passive"))
    )
    (net (code "26") (name "Net-(C27-Pad2)") (class "Default")
      (node (ref "C27") (pin "2") (pinfunction "2_2") (pintype "passive"))
      (node (ref "R8") (pin "1") (pinfunction "1_1") (pintype "passive"))
    )
    (net (code "27") (name "Net-(C30-Pad2)") (class "Default")
      (node (ref "C30") (pin "2") (pinfunction "2_2") (pintype "passive"))
      (node (ref "R12") (pin "2") (pinfunction "2_2") (pintype "passive"))
    )
    (net (code "28") (name "Net-(C42-Pad2)") (class "Default")
      (node (ref "C42") (pin "2") (pinfunction "2_2") (pintype "passive"))
      (node (ref "R19") (pin "1") (pinfunction "1_1") (pintype "passive"))
    )
    (net (code "29") (name "Net-(C45-Pad2)") (class "Default")
      (node (ref "C45") (pin "2") (pinfunction "2_2") (pintype "passive"))
      (node (ref "R23") (pin "2") (pinfunction "2_2") (pintype "passive"))
    )
    (net (code "30") (name "Net-(J1-Pad1)") (class "Default")
      (node (ref "J1") (pin "1") (pinfunction "1_1") (pintype "passive"))
      (node (ref "R1") (pin "2") (pinfunction "2_2") (pintype "passive"))
    )
    (net (code "31") (name "Net-(J1-Pad2)") (class "Default")
      (node (ref "J1") (pin "2") (pinfunction "2_2") (pintype "passive"))
      (node (ref "R11") (pin "2") (pinfunction "2_2") (pintype "passive"))
    )
    (net (code "32") (name "Net-(J1-Pad3)") (class "Default")
      (node (ref "J1") (pin "3") (pinfunction "3_3") (pintype "passive"))
      (node (ref "R22") (pin "2") (pinfunction "2_2") (pintype "passive"))
    )
    (net (code "33") (name "Net-(J3-1)") (class "Default")
      (node (ref "J3") (pin "P$1") (pinfunction "1_P$1") (pintype "passive"))
      (node (ref "PR5") (pin "2") (pinfunction "2_2") (pintype "passive"))
      (node (ref "PR6") (pin "1") (pinfunction "1_1") (pintype "passive"))
      (node (ref "R51") (pin "2") (pinfunction "2_2") (pintype "passive"))
      (node (ref "R56") (pin "1") (pinfunction "1_1") (pintype "passive"))
      (node (ref "U1") (pin "P$8") (pinfunction "ONSENSE_P$8") (pintype "bidirectional"))
    )
    (net (code "34") (name "Net-(J4-1)") (class "Default")
      (node (ref "J4") (pin "P$1") (pinfunction "1_P$1") (pintype "passive"))
      (node (ref "PR1") (pin "2") (pinfunction "2_2") (pintype "passive"))
      (node (ref "PR2") (pin "1") (pinfunction "1_1") (pintype "passive"))
      (node (ref "R13") (pin "1") (pinfunction "1_1") (pintype "passive"))
      (node (ref "R8") (pin "2") (pinfunction "2_2") (pintype "passive"))
      (node (ref "U2") (pin "P$8") (pinfunction "ONSENSE_P$8") (pintype "bidirectional"))
    )
    (net (code "35") (name "Net-(J5-1)") (class "Default")
      (node (ref "J5") (pin "P$1") (pinfunction "1_P$1") (pintype "passive"))
      (node (ref "PR3") (pin "2") (pinfunction "2_2") (pintype "passive"))
      (node (ref "PR4") (pin "1") (pinfunction "1_1") (pintype "passive"))
      (node (ref "R19") (pin "2") (pinfunction "2_2") (pintype "passive"))
      (node (ref "R24") (pin "1") (pinfunction "1_1") (pintype "passive"))
      (node (ref "U3") (pin "P$8") (pinfunction "ONSENSE_P$8") (pintype "bidirectional"))
    )
    (net (code "36") (name "Net-(R13-Pad2)") (class "Default")
      (node (ref "R13") (pin "2") (pinfunction "2_2") (pintype "passive"))
      (node (ref "VR3") (pin "B") (pinfunction "B_B") (pintype "passive"))
      (node (ref "VR3") (pin "C") (pinfunction "C_C") (pintype "passive"))
    )
    (net (code "37") (name "Net-(R24-Pad2)") (class "Default")
      (node (ref "R24") (pin "2") (pinfunction "2_2") (pintype "passive"))
      (node (ref "VR5") (pin "B") (pinfunction "B_B") (pintype "passive"))
      (node (ref "VR5") (pin "C") (pinfunction "C_C") (pintype "passive"))
    )
    (net (code "38") (name "Net-(R56-Pad2)") (class "Default")
      (node (ref "R56") (pin "2") (pinfunction "2_2") (pintype "passive"))
      (node (ref "VR1") (pin "B") (pinfunction "B_B") (pintype "passive"))
      (node (ref "VR1") (pin "C") (pinfunction "C_C") (pintype "passive"))
    )
    (net (code "39") (name "Net-(U1-BIASP)") (class "Default")
      (node (ref "C9") (pin "2") (pinfunction "2_2") (pintype "passive"))
      (node (ref "R44") (pin "2") (pinfunction "2_2") (pintype "passive"))
      (node (ref "U1") (pin "P12") (pinfunction "BIASP_P12") (pintype "bidirectional"))
    )
    (net (code "40") (name "Net-(U1-COMP)") (class "Default")
      (node (ref "C8") (pin "2") (pinfunction "2_2") (pintype "passive"))
      (node (ref "U1") (pin "P6") (pinfunction "COMP_P6") (pintype "bidirectional"))
    )
    (net (code "41") (name "Net-(U1-IN+)") (class "Default")
      (node (ref "C1") (pin "2") (pinfunction "2_2") (pintype "passive"))
      (node (ref "R1") (pin "1") (pinfunction "1_1") (pintype "passive"))
      (node (ref "R2") (pin "1") (pinfunction "1_1") (pintype "passive"))
      (node (ref "U1") (pin "P4") (pinfunction "IN+_P4") (pintype "bidirectional"))
    )
    (net (code "42") (name "Net-(U1-IN-)") (class "Default")
      (node (ref "R55") (pin "1") (pinfunction "1_1") (pintype "passive"))
      (node (ref "U1") (pin "P5") (pinfunction "IN-_P5") (pintype "bidirectional"))
      (node (ref "VR1") (pin "A") (pinfunction "A_A") (pintype "passive"))
    )
    (net (code "43") (name "Net-(U1-MUTE)") (class "Default")
      (node (ref "C6") (pin "+") (pinfunction "+_+") (pintype "passive"))
      (node (ref "R52") (pin "2") (pinfunction "2_2") (pintype "passive"))
      (node (ref "U1") (pin "P2") (pinfunction "MUTE_P2") (pintype "bidirectional"))
    )
    (net (code "44") (name "Net-(U1-NOUT)") (class "Default")
      (node (ref "R48") (pin "2") (pinfunction "2_2") (pintype "passive"))
      (node (ref "U1") (pin "P14") (pinfunction "NOUT_P14") (pintype "bidirectional"))
    )
    (net (code "45") (name "Net-(U1-POUT)") (class "Default")
      (node (ref "R47") (pin "2") (pinfunction "2_2") (pintype "passive"))
      (node (ref "U1") (pin "P13") (pinfunction "POUT_P13") (pintype "bidirectional"))
    )
    (net (code "46") (name "Net-(U2-BIASP)") (class "Default")
      (node (ref "C20") (pin "2") (pinfunction "2_2") (pintype "passive"))
      (node (ref "R3") (pin "2") (pinfunction "2_2") (pintype "passive"))
      (node (ref "U2") (pin "P12") (pinfunction "BIASP_P12") (pintype "bidirectional"))
    )
    (net (code "47") (name "Net-(U2-COMP)") (class "Default")
      (node (ref "C22") (pin "2") (pinfunction "2_2") (pintype "passive"))
      (node (ref "U2") (pin "P6") (pinfunction "COMP_P6") (pintype "bidirectional"))
    )
    (net (code "48") (name "Net-(U2-IN+)") (class "Default")
      (node (ref "C29") (pin "2") (pinfunction "2_2") (pintype "passive"))
      (node (ref "R10") (pin "1") (pinfunction "1_1") (pintype "passive"))
      (node (ref "R11") (pin "1") (pinfunction "1_1") (pintype "passive"))
      (node (ref "U2") (pin "P4") (pinfunction "IN+_P4") (pintype "bidirectional"))
    )
    (net (code "49") (name "Net-(U2-IN-)") (class "Default")
      (node (ref "R12") (pin "1") (pinfunction "1_1") (pintype "passive"))
      (node (ref "U2") (pin "P5") (pinfunction "IN-_P5") (pintype "bidirectional"))
      (node (ref "VR3") (pin "A") (pinfunction "A_A") (pintype "passive"))
    )
    (net (code "50") (name "Net-(U2-MUTE)") (class "Default")
      (node (ref "C28") (pin "+") (pinfunction "+_+") (pintype "passive"))
      (node (ref "R9") (pin "2") (pinfunction "2_2") (pintype "passive"))
      (node (ref "U2") (pin "P2") (pinfunction "MUTE_P2") (pintype "bidirectional"))
    )
    (net (code "51") (name "Net-(U2-NOUT)") (class "Default")
      (node (ref "R7") (pin "2") (pinfunction "2_2") (pintype "passive"))
      (node (ref "U2") (pin "P14") (pinfunction "NOUT_P14") (pintype "bidirectional"))
    )
    (net (code "52") (name "Net-(U2-POUT)") (class "Default")
      (node (ref "R6") (pin "2") (pinfunction "2_2") (pintype "passive"))
      (node (ref "U2") (pin "P13") (pinfunction "POUT_P13") (pintype "bidirectional"))
    )
    (net (code "53") (name "Net-(U3-BIASP)") (class "Default")
      (node (ref "C35") (pin "2") (pinfunction "2_2") (pintype "passive"))
      (node (ref "R14") (pin "2") (pinfunction "2_2") (pintype "passive"))
      (node (ref "U3") (pin "P12") (pinfunction "BIASP_P12") (pintype "bidirectional"))
    )
    (net (code "54") (name "Net-(U3-COMP)") (class "Default")
      (node (ref "C37") (pin "2") (pinfunction "2_2") (pintype "passive"))
      (node (ref "U3") (pin "P6") (pinfunction "COMP_P6") (pintype "bidirectional"))
    )
    (net (code "55") (name "Net-(U3-IN+)") (class "Default")
      (node (ref "C44") (pin "2") (pinfunction "2_2") (pintype "passive"))
      (node (ref "R21") (pin "1") (pinfunction "1_1") (pintype "passive"))
      (node (ref "R22") (pin "1") (pinfunction "1_1") (pintype "passive"))
      (node (ref "U3") (pin "P4") (pinfunction "IN+_P4") (pintype "bidirectional"))
    )
    (net (code "56") (name "Net-(U3-IN-)") (class "Default")
      (node (ref "R23") (pin "1") (pinfunction "1_1") (pintype "passive"))
      (node (ref "U3") (pin "P5") (pinfunction "IN-_P5") (pintype "bidirectional"))
      (node (ref "VR5") (pin "A") (pinfunction "A_A") (pintype "passive"))
    )
    (net (code "57") (name "Net-(U3-MUTE)") (class "Default")
      (node (ref "C43") (pin "+") (pinfunction "+_+") (pintype "passive"))
      (node (ref "R20") (pin "2") (pinfunction "2_2") (pintype "passive"))
      (node (ref "U3") (pin "P2") (pinfunction "MUTE_P2") (pintype "bidirectional"))
    )
    (net (code "58") (name "Net-(U3-NOUT)") (class "Default")
      (node (ref "R18") (pin "2") (pinfunction "2_2") (pintype "passive"))
      (node (ref "U3") (pin "P14") (pinfunction "NOUT_P14") (pintype "bidirectional"))
    )
    (net (code "59") (name "Net-(U3-POUT)") (class "Default")
      (node (ref "R17") (pin "2") (pinfunction "2_2") (pintype "passive"))
      (node (ref "U3") (pin "P13") (pinfunction "POUT_P13") (pintype "bidirectional"))
    )
    (net (code "60") (name "V+") (class "Default")
      (node (ref "C11") (pin "1") (pinfunction "1_1") (pintype "passive"))
      (node (ref "C12") (pin "+") (pinfunction "+_+") (pintype "passive"))
      (node (ref "C17") (pin "+") (pinfunction "+_+") (pintype "passive"))
      (node (ref "C19") (pin "1") (pinfunction "1_1") (pintype "passive"))
      (node (ref "C23") (pin "+") (pinfunction "+_+") (pintype "passive"))
      (node (ref "C25") (pin "1") (pinfunction "1_1") (pintype "passive"))
      (node (ref "C32") (pin "+") (pinfunction "+_+") (pintype "passive"))
      (node (ref "C34") (pin "1") (pinfunction "1_1") (pintype "passive"))
      (node (ref "C38") (pin "+") (pinfunction "+_+") (pintype "passive"))
      (node (ref "C4") (pin "+") (pinfunction "+_+") (pintype "passive"))
      (node (ref "C40") (pin "1") (pinfunction "1_1") (pintype "passive"))
      (node (ref "C5") (pin "1") (pinfunction "1_1") (pintype "passive"))
      (node (ref "J12") (pin "P$1") (pinfunction "1_P$1") (pintype "passive"))
      (node (ref "J13") (pin "P$1") (pinfunction "1_P$1") (pintype "passive"))
      (node (ref "J14") (pin "P$1") (pinfunction "1_P$1") (pintype "passive"))
      (node (ref "J2") (pin "P$4") (pinfunction "4_P$4") (pintype "passive"))
      (node (ref "U1") (pin "P15") (pinfunction "+VCC_P15") (pintype "passive"))
      (node (ref "U2") (pin "P15") (pinfunction "+VCC_P15") (pintype "passive"))
      (node (ref "U3") (pin "P15") (pinfunction "+VCC_P15") (pintype "passive"))
    )
    (net (code "61") (name "V-") (class "Default")
      (node (ref "C13") (pin "2") (pinfunction "2_2") (pintype "passive"))
      (node (ref "C14") (pin "-") (pinfunction "-_-") (pintype "passive"))
      (node (ref "C16") (pin "-") (pinfunction "-_-") (pintype "passive"))
      (node (ref "C18") (pin "2") (pinfunction "2_2") (pintype "passive"))
      (node (ref "C2") (pin "-") (pinfunction "-_-") (pintype "passive"))
      (node (ref "C24") (pin "-") (pinfunction "-_-") (pintype "passive"))
      (node (ref "C26") (pin "2") (pinfunction "2_2") (pintype "passive"))
      (node (ref "C3") (pin "2") (pinfunction "2_2") (pintype "passive"))
      (node (ref "C31") (pin "-") (pinfunction "-_-") (pintype "passive"))
      (node (ref "C33") (pin "2") (pinfunction "2_2") (pintype "passive"))
      (node (ref "C39") (pin "-") (pinfunction "-_-") (pintype "passive"))
      (node (ref "C41") (pin "2") (pinfunction "2_2") (pintype "passive"))
      (node (ref "J12") (pin "P$9") (pinfunction "9_P$9") (pintype "passive"))
      (node (ref "J13") (pin "P$9") (pinfunction "9_P$9") (pintype "passive"))
      (node (ref "J14") (pin "P$9") (pinfunction "9_P$9") (pintype "passive"))
      (node (ref "J2") (pin "P$3") (pinfunction "3_P$3") (pintype "passive"))
      (node (ref "U1") (pin "P10") (pinfunction "-VEE_P10") (pintype "power_in"))
      (node (ref "U2") (pin "P10") (pinfunction "-VEE_P10") (pintype "power_in"))
      (node (ref "U3") (pin "P10") (pinfunction "-VEE_P10") (pintype "power_in"))
    )
  )
)
